# RS232.net
KiCad netlist of a schematic drawn in Altium Designer
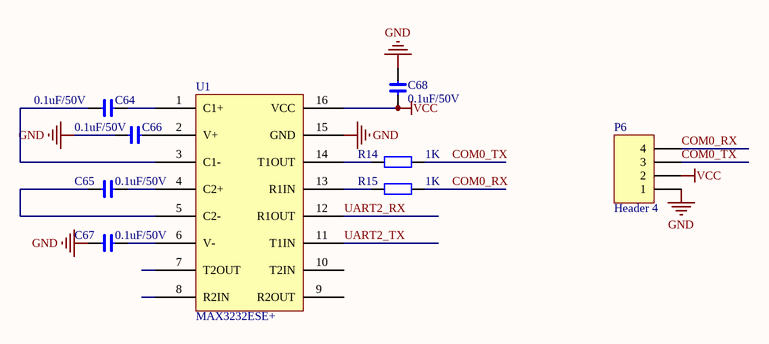
[diagram p0: RS232.SchDoc]

(export (version "E")
  (design (tool "Eeschema 10.0.6"))
  (components
    (comp (ref "C64")
      (value "0.1uF/50V")
      (footprint "0603C")
      (description "C")
      (libsource (lib "Top") (part "C"))
    )
    (comp (ref "C65")
      (value "0.1uF/50V")
      (footprint "0603C")
      (description "C")
      (libsource (lib "Top") (part "C"))
    )
    (comp (ref "C66")
      (value "0.1uF/50V")
      (footprint "0603C")
      (description "C")
      (libsource (lib "Top") (part "C"))
    )
    (comp (ref "C67")
      (value "0.1uF/50V")
      (footprint "0603C")
      (description "C")
      (libsource (lib "Top") (part "C"))
    )
    (comp (ref "C68")
      (value "0.1uF/50V")
      (footprint "0603C")
      (description "C")
      (libsource (lib "Top") (part "C"))
    )
    (comp (ref "P6")
      (value "Header 4")
      (footprint "HDR1X4")
      (description "Header, 4-Pin")
      (fields (field (name "PUBLISHER") "Altium Limited"))
      (libsource (lib "Miscellaneous Connectors") (part "Header 4"))
    )
    (comp (ref "R14")
      (value "1K")
      (footprint "0603R")
      (description "Resistor")
      (fields (field (name "PUBLISHER") "Altium Limited"))
      (libsource (lib "Miscellaneous Devices") (part "Res2"))
    )
    (comp (ref "R15")
      (value "1K")
      (footprint "0603R")
      (description "Resistor")
      (fields (field (name "PUBLISHER") "Altium Limited"))
      (libsource (lib "Miscellaneous Devices") (part "Res2"))
    )
    (comp (ref "U1")
      (value "MAX3232ESE+")
      (footprint "SOIC127P600X265-16N")
      (libsource (lib "Schlib_20110825") (part "MAX3232ESE+"))
    )
  )
  (nets
    (net (code "1") (name "/COM0_RX") (class "Default")
      (node (ref "P6") (pin "4") (pinfunction "4_4") (pintype "passive"))
      (node (ref "R15") (pin "1") (pinfunction "1_1") (pintype "passive"))
    )
    (net (code "2") (name "/COM0_TX") (class "Default")
      (node (ref "P6") (pin "3") (pinfunction "3_3") (pintype "passive"))
      (node (ref "R14") (pin "1") (pinfunction "1_1") (pintype "passive"))
    )
    (net (code "3") (name "/UART2_RX") (class "Default")
      (node (ref "U1") (pin "12") (pinfunction "R1OUT_12") (pintype "passive"))
    )
    (net (code "4") (name "/UART2_TX") (class "Default")
      (node (ref "U1") (pin "11") (pinfunction "T1IN_11") (pintype "passive"))
    )
    (net (code "5") (name "GND") (class "Default")
      (node (ref "C66") (pin "2") (pintype "passive"))
      (node (ref "C67") (pin "2") (pintype "passive"))
      (node (ref "C68") (pin "1") (pintype "passive"))
      (node (ref "P6") (pin "1") (pinfunction "1_1") (pintype "passive"))
      (node (ref "U1") (pin "15") (pinfunction "GND_15") (pintype "passive"))
    )
    (net (code "6") (name "Net-(U1-C1+)") (class "Default")
      (node (ref "C64") (pin "1") (pintype "passive"))
      (node (ref "U1") (pin "1") (pinfunction "C1+_1") (pintype "passive"))
    )
    (net (code "7") (name "Net-(U1-C1-)") (class "Default")
      (node (ref "C64") (pin "2") (pintype "passive"))
      (node (ref "U1") (pin "3") (pinfunction "C1-_3") (pintype "passive"))
    )
    (net (code "8") (name "Net-(U1-C2+)") (class "Default")
      (node (ref "C65") (pin "1") (pintype "passive"))
      (node (ref "U1") (pin "4") (pinfunction "C2+_4") (pintype "passive"))
    )
    (net (code "9") (name "Net-(U1-C2-)") (class "Default")
      (node (ref "C65") (pin "2") (pintype "passive"))
      (node (ref "U1") (pin "5") (pinfunction "C2-_5") (pintype "passive"))
    )
    (net (code "10") (name "Net-(U1-R1IN)") (class "Default")
      (node (ref "R15") (pin "2") (pinfunction "2_2") (pintype "passive"))
      (node (ref "U1") (pin "13") (pinfunction "R1IN_13") (pintype "passive"))
    )
    (net (code "11") (name "Net-(U1-T1OUT)") (class "Default")
      (node (ref "R14") (pin "2") (pinfunction "2_2") (pintype "passive"))
      (node (ref "U1") (pin "14") (pinfunction "T1OUT_14") (pintype "passive"))
    )
    (net (code "12") (name "Net-(U1-V+)") (class "Default")
      (node (ref "C66") (pin "1") (pintype "passive"))
      (node (ref "U1") (pin "2") (pinfunction "V+_2") (pintype "passive"))
    )
    (net (code "13") (name "Net-(U1-V-)") (class "Default")
      (node (ref "C67") (pin "1") (pintype "passive"))
      (node (ref "U1") (pin "6") (pinfunction "V-_6") (pintype "passive"))
    )
    (net (code "14") (name "VCC") (class "Default")
      (node (ref "C68") (pin "2") (pintype "passive"))
      (node (ref "P6") (pin "2") (pinfunction "2_2") (pintype "passive"))
      (node (ref "U1") (pin "16") (pinfunction "VCC_16") (pintype "passive"))
    )
    (net (code "15") (name "unconnected-(U1-R2IN-Pad8)") (class "Default")
      (node (ref "U1") (pin "8") (pinfunction "R2IN_8") (pintype "passive"))
    )
    (net (code "16") (name "unconnected-(U1-R2OUT-Pad9)") (class "Default")
      (node (ref "U1") (pin "9") (pinfunction "R2OUT_9") (pintype "passive"))
    )
    (net (code "17") (name "unconnected-(U1-T2IN-Pad10)") (class "Default")
      (node (ref "U1") (pin "10") (pinfunction "T2IN_10") (pintype "passive"))
    )
    (net (code "18") (name "unconnected-(U1-T2OUT-Pad7)") (class "Default")
      (node (ref "U1") (pin "7") (pinfunction "T2OUT_7") (pintype "passive"))
    )
  )
)
